# XDS110-TAG_connector_adapter.net
KiCad netlist of a schematic drawn in Altium Designer
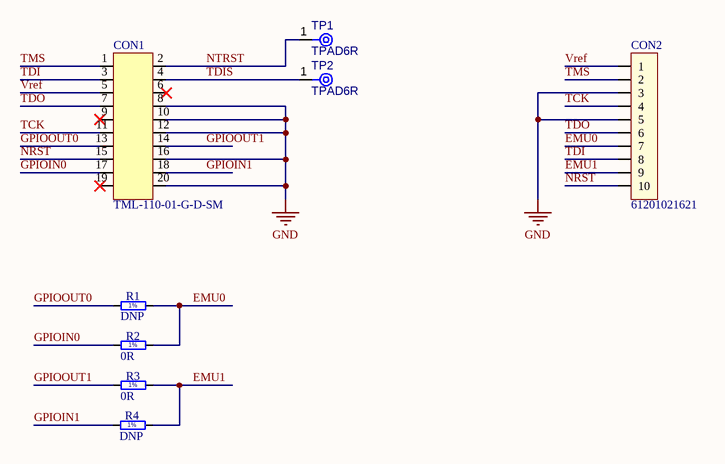
[diagram p0: XDS110-TAG connector adapter.SchDoc]

(export (version "E")
  (design (tool "Eeschema 10.0.6"))
  (components
    (comp (ref "CON1")
      (value "TML-110-01-G-D-SM")
      (footprint "TML-110-01-G-D-SM")
      (description "\".050\"\" X .100\"\" Shrouded Terminal Strip\"")
      (fields (field (name "MFG") "Samtec"))
      (libsource (lib "DME-projects") (part "CON20"))
    )
    (comp (ref "CON2")
      (value "61201021621")
      (footprint "61201021621")
      (description "Male Box Header WR-BHD, THT, Vertical, pitch 2.54 mm, 10 pins")
      (fields (field (name "MFG") "Wurth Elektronik"))
      (libsource (lib "DME-projects") (part "CON10"))
    )
    (comp (ref "R1")
      (value "DNP")
      (footprint "R0603")
      (description "generic 0603 Thick film resistor")
      (fields (field (name "POWER") "100mW") (field (name "MFG") "generic"))
      (libsource (lib "DME-projects") (part "res_1pct"))
    )
    (comp (ref "R2")
      (value "0R")
      (footprint "R0603")
      (description "generic 0603 Thick film resistor")
      (fields (field (name "POWER") "100mW") (field (name "MFG") "generic"))
      (libsource (lib "DME-projects") (part "res_1pct"))
    )
    (comp (ref "R3")
      (value "0R")
      (footprint "R0603")
      (description "generic 0603 Thick film resistor")
      (fields (field (name "POWER") "100mW") (field (name "MFG") "generic"))
      (libsource (lib "DME-projects") (part "res_1pct"))
    )
    (comp (ref "R4")
      (value "DNP")
      (footprint "R0603")
      (description "generic 0603 Thick film resistor")
      (fields (field (name "POWER") "100mW") (field (name "MFG") "generic"))
      (libsource (lib "DME-projects") (part "res_1pct"))
    )
    (comp (ref "TP1")
      (value "TPAD6R")
      (footprint "TP06R")
      (description "0.6mm round")
      (libsource (lib "DME-projects") (part "CMP-001-0001-4"))
    )
    (comp (ref "TP2")
      (value "TPAD6R")
      (footprint "TP06R")
      (description "0.6mm round")
      (libsource (lib "DME-projects") (part "CMP-001-0001-4"))
    )
  )
  (nets
    (net (code "1") (name "/EMU0") (class "Default")
      (node (ref "CON2") (pin "7") (pinfunction "7_7") (pintype "passive"))
      (node (ref "R1") (pin "2") (pinfunction "2_2") (pintype "passive"))
      (node (ref "R2") (pin "2") (pinfunction "2_2") (pintype "passive"))
    )
    (net (code "2") (name "/EMU1") (class "Default")
      (node (ref "CON2") (pin "9") (pinfunction "9_9") (pintype "passive"))
      (node (ref "R3") (pin "2") (pinfunction "2_2") (pintype "passive"))
      (node (ref "R4") (pin "2") (pinfunction "2_2") (pintype "passive"))
    )
    (net (code "3") (name "/GPIOIN0") (class "Default")
      (node (ref "CON1") (pin "17") (pinfunction "17_17") (pintype "passive"))
      (node (ref "R2") (pin "1") (pinfunction "1_1") (pintype "passive"))
    )
    (net (code "4") (name "/GPIOIN1") (class "Default")
      (node (ref "CON1") (pin "18") (pinfunction "18_18") (pintype "passive"))
      (node (ref "R4") (pin "1") (pinfunction "1_1") (pintype "passive"))
    )
    (net (code "5") (name "/GPIOOUT0") (class "Default")
      (node (ref "CON1") (pin "13") (pinfunction "13_13") (pintype "passive"))
      (node (ref "R1") (pin "1") (pinfunction "1_1") (pintype "passive"))
    )
    (net (code "6") (name "/GPIOOUT1") (class "Default")
      (node (ref "CON1") (pin "14") (pinfunction "14_14") (pintype "passive"))
      (node (ref "R3") (pin "1") (pinfunction "1_1") (pintype "passive"))
    )
    (net (code "7") (name "/NRST") (class "Default")
      (node (ref "CON1") (pin "15") (pinfunction "15_15") (pintype "passive"))
      (node (ref "CON2") (pin "10") (pinfunction "10_10") (pintype "passive"))
    )
    (net (code "8") (name "/NTRST") (class "Default")
      (node (ref "CON1") (pin "2") (pinfunction "2_2") (pintype "passive"))
      (node (ref "TP1") (pin "1") (pinfunction "TP_1") (pintype "passive"))
    )
    (net (code "9") (name "/TCK") (class "Default")
      (node (ref "CON1") (pin "11") (pinfunction "11_11") (pintype "passive"))
      (node (ref "CON2") (pin "4") (pinfunction "4_4") (pintype "passive"))
    )
    (net (code "10") (name "/TDI") (class "Default")
      (node (ref "CON1") (pin "3") (pinfunction "3_3") (pintype "passive"))
      (node (ref "CON2") (pin "8") (pinfunction "8_8") (pintype "passive"))
    )
    (net (code "11") (name "/TDIS") (class "Default")
      (node (ref "CON1") (pin "4") (pinfunction "4_4") (pintype "passive"))
      (node (ref "TP2") (pin "1") (pinfunction "TP_1") (pintype "passive"))
    )
    (net (code "12") (name "/TDO") (class "Default")
      (node (ref "CON1") (pin "7") (pinfunction "7_7") (pintype "passive"))
      (node (ref "CON2") (pin "6") (pinfunction "6_6") (pintype "passive"))
    )
    (net (code "13") (name "/TMS") (class "Default")
      (node (ref "CON1") (pin "1") (pinfunction "1_1") (pintype "passive"))
      (node (ref "CON2") (pin "2") (pinfunction "2_2") (pintype "passive"))
    )
    (net (code "14") (name "/Vref") (class "Default")
      (node (ref "CON1") (pin "5") (pinfunction "5_5") (pintype "passive"))
      (node (ref "CON2") (pin "1") (pinfunction "1_1") (pintype "passive"))
    )
    (net (code "15") (name "GND") (class "Default")
      (node (ref "CON1") (pin "10") (pinfunction "10_10") (pintype "passive"))
      (node (ref "CON1") (pin "12") (pinfunction "12_12") (pintype "passive"))
      (node (ref "CON1") (pin "16") (pinfunction "16_16") (pintype "passive"))
      (node (ref "CON1") (pin "20") (pinfunction "20_20") (pintype "passive"))
      (node (ref "CON1") (pin "8") (pinfunction "8_8") (pintype "passive"))
      (node (ref "CON2") (pin "3") (pinfunction "3_3") (pintype "passive"))
      (node (ref "CON2") (pin "5") (pinfunction "5_5") (pintype "passive"))
    )
    (net (code "16") (name "unconnected-(CON1-Pad6)") (class "Default")
      (node (ref "CON1") (pin "6") (pinfunction "6_6") (pintype "passive+no_connect"))
    )
    (net (code "17") (name "unconnected-(CON1-Pad9)") (class "Default")
      (node (ref "CON1") (pin "9") (pinfunction "9_9") (pintype "passive+no_connect"))
    )
    (net (code "18") (name "unconnected-(CON1-Pad19)") (class "Default")
      (node (ref "CON1") (pin "19") (pinfunction "19_19") (pintype "passive+no_connect"))
    )
  )
)
